# TG3_2.net
KiCad netlist of a schematic drawn in EAGLE
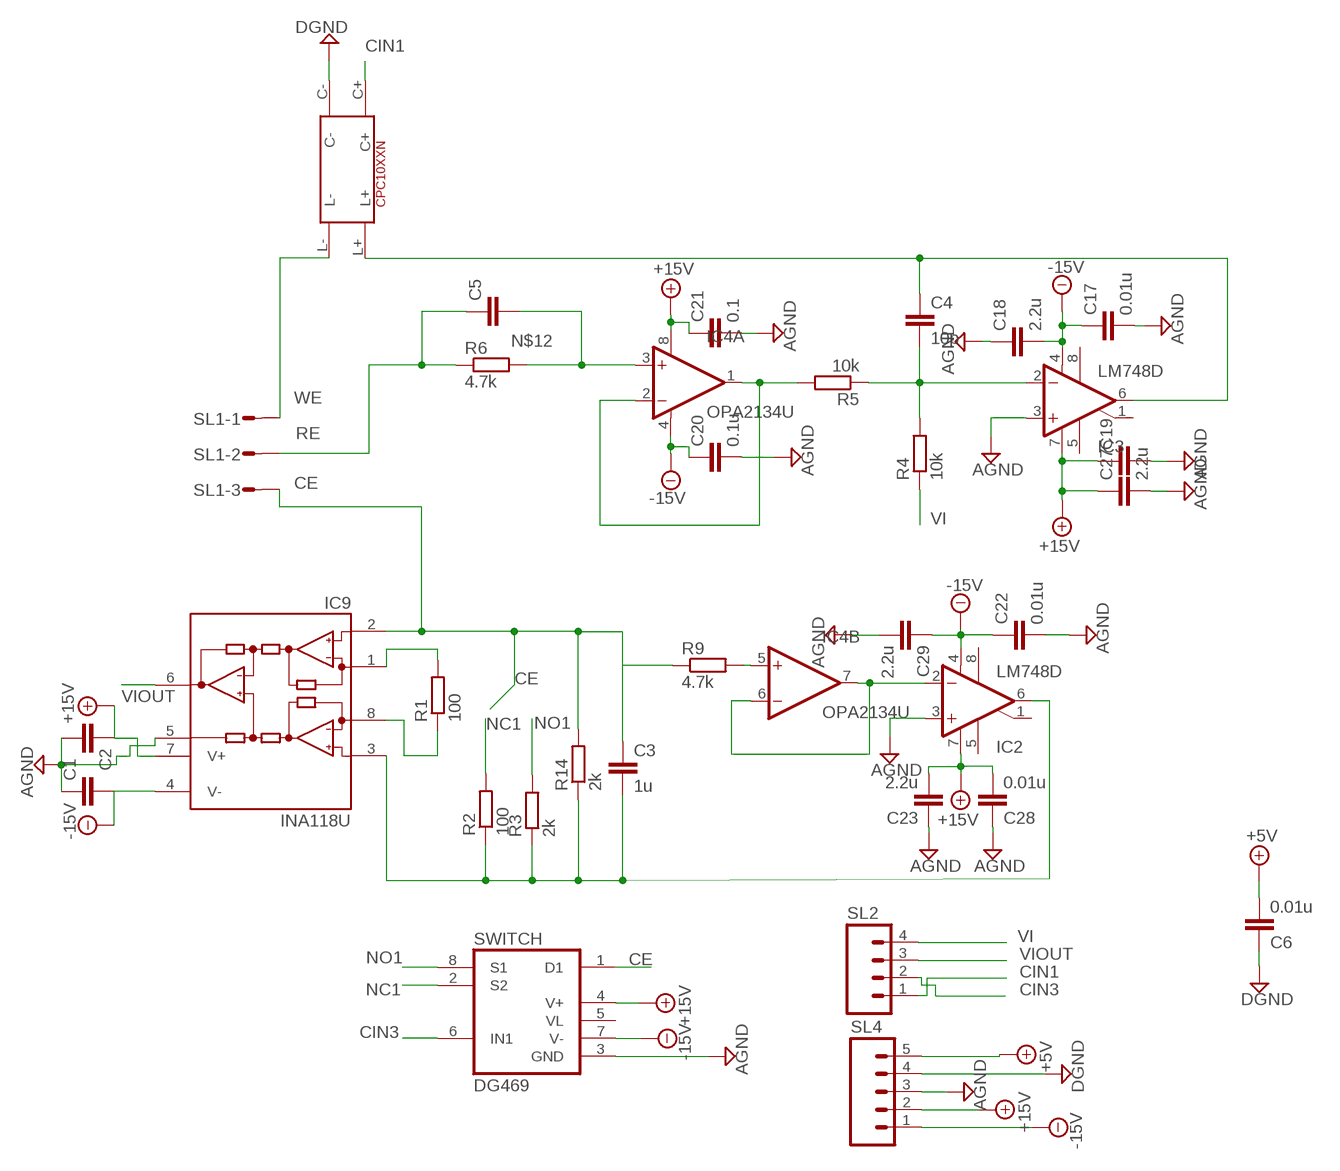
[diagram p0: schematic, sheet 1]

(export (version "E")
  (design (tool "Eeschema 10.0.6"))
  (components
    (comp (ref "C1") (value "C") (footprint "eagle-import:C0805") (libsource (lib "eagle-import") (part "C")))
    (comp (ref "C2") (value "C") (footprint "eagle-import:C0805") (libsource (lib "eagle-import") (part "C")))
    (comp (ref "C3")
      (value "1u")
      (footprint "eagle-import:C0805")
      (libsource (lib "eagle-import") (part "C"))
    )
    (comp (ref "C4")
      (value "10p")
      (footprint "eagle-import:C0805")
      (libsource (lib "eagle-import") (part "C"))
    )
    (comp (ref "C5") (value "C") (footprint "eagle-import:C0805") (libsource (lib "eagle-import") (part "C")))
    (comp (ref "C6")
      (value "0.01u")
      (footprint "eagle-import:C0805")
      (libsource (lib "eagle-import") (part "C"))
    )
    (comp (ref "C17")
      (value "0.01u")
      (footprint "eagle-import:C0805")
      (libsource (lib "eagle-import") (part "C"))
    )
    (comp (ref "C18")
      (value "2.2u")
      (footprint "eagle-import:C0805")
      (libsource (lib "eagle-import") (part "C"))
    )
    (comp (ref "C19")
      (value "C")
      (footprint "eagle-import:C0805")
      (libsource (lib "eagle-import") (part "C"))
    )
    (comp (ref "C20")
      (value "0.1u")
      (footprint "eagle-import:C0805")
      (libsource (lib "eagle-import") (part "C"))
    )
    (comp (ref "C21")
      (value "0.1")
      (footprint "eagle-import:C0805")
      (libsource (lib "eagle-import") (part "C"))
    )
    (comp (ref "C22")
      (value "0.01u")
      (footprint "eagle-import:C0805")
      (libsource (lib "eagle-import") (part "C"))
    )
    (comp (ref "C23")
      (value "2.2u")
      (footprint "eagle-import:C0805")
      (libsource (lib "eagle-import") (part "C"))
    )
    (comp (ref "C27")
      (value "2.2u")
      (footprint "eagle-import:C0805")
      (libsource (lib "eagle-import") (part "C"))
    )
    (comp (ref "C28")
      (value "0.01u")
      (footprint "eagle-import:C0805")
      (libsource (lib "eagle-import") (part "C"))
    )
    (comp (ref "C29")
      (value "2.2u")
      (footprint "eagle-import:C0805")
      (libsource (lib "eagle-import") (part "C"))
    )
    (comp (ref "IC2")
      (value "LM748D")
      (footprint "eagle-import:SO08")
      (libsource (lib "eagle-import") (part "748DLM"))
    )
    (comp (ref "IC3")
      (value "LM748D")
      (footprint "eagle-import:SO08")
      (libsource (lib "eagle-import") (part "748DLM"))
    )
    (comp (ref "IC4")
      (value "OPA2134U")
      (footprint "eagle-import:SO08")
      (fields (field (name "MF") "TEXAS INSTRUMENTS") (field (name "MPN") "OPA2134UA"))
      (libsource (lib "eagle-import") (part "OPA2134U"))
    )
    (comp (ref "IC9")
      (value "INA118U")
      (footprint "eagle-import:SO08")
      (fields (field (name "MF") "TEXAS INSTRUMENTS"))
      (libsource (lib "eagle-import") (part "INA118U"))
    )
    (comp (ref "R1")
      (value "100")
      (footprint "eagle-import:R0805")
      (libsource (lib "eagle-import") (part "R"))
    )
    (comp (ref "R2")
      (value "100")
      (footprint "eagle-import:R0805")
      (libsource (lib "eagle-import") (part "R"))
    )
    (comp (ref "R3")
      (value "2k")
      (footprint "eagle-import:R0805")
      (libsource (lib "eagle-import") (part "R"))
    )
    (comp (ref "R4")
      (value "10k")
      (footprint "eagle-import:R0805")
      (libsource (lib "eagle-import") (part "R"))
    )
    (comp (ref "R5")
      (value "10k")
      (footprint "eagle-import:R0805")
      (libsource (lib "eagle-import") (part "R"))
    )
    (comp (ref "R6")
      (value "4.7k")
      (footprint "eagle-import:R0805")
      (libsource (lib "eagle-import") (part "R"))
    )
    (comp (ref "R9")
      (value "4.7k")
      (footprint "eagle-import:R0805")
      (libsource (lib "eagle-import") (part "R"))
    )
    (comp (ref "R14")
      (value "2k")
      (footprint "eagle-import:R0805")
      (libsource (lib "eagle-import") (part "R"))
    )
    (comp (ref "SL1")
      (value "M03S")
      (footprint "eagle-import:03P")
      (libsource (lib "eagle-import") (part "M03S"))
    )
    (comp (ref "SL2")
      (value "M04")
      (footprint "eagle-import:04P")
      (libsource (lib "eagle-import") (part "M04"))
    )
    (comp (ref "SL4")
      (value "M05")
      (footprint "eagle-import:05P")
      (libsource (lib "eagle-import") (part "M05"))
    )
    (comp (ref "SWITCH")
      (value "DG469")
      (footprint "eagle-import:SO08")
      (libsource (lib "eagle-import") (part "DG469"))
    )
    (comp (ref "U$5")
      (value "CPC10XXN")
      (footprint "eagle-import:CPC10XXN")
      (libsource (lib "eagle-import") (part "CPC10XXN"))
    )
  )
  (nets
    (net (code "1") (name "+5V") (class "Default")
      (node (ref "C6") (pin "2") (pinfunction "2_2") (pintype "passive"))
      (node (ref "SL4") (pin "5") (pinfunction "5_5") (pintype "passive"))
    )
    (net (code "2") (name "+15V") (class "Default")
      (node (ref "C19") (pin "1") (pinfunction "1_1") (pintype "passive"))
      (node (ref "C2") (pin "1") (pinfunction "1_1") (pintype "passive"))
      (node (ref "C21") (pin "1") (pinfunction "1_1") (pintype "passive"))
      (node (ref "C23") (pin "2") (pinfunction "2_2") (pintype "passive"))
      (node (ref "C27") (pin "1") (pinfunction "1_1") (pintype "passive"))
      (node (ref "C28") (pin "2") (pinfunction "2_2") (pintype "passive"))
      (node (ref "IC2") (pin "7") (pinfunction "V+_7") (pintype "power_in"))
      (node (ref "IC3") (pin "7") (pinfunction "V+_7") (pintype "power_in"))
      (node (ref "IC4") (pin "8") (pinfunction "V+_8") (pintype "power_in"))
      (node (ref "IC9") (pin "7") (pinfunction "V+_7") (pintype "power_in"))
      (node (ref "SL4") (pin "2") (pinfunction "2_2") (pintype "passive"))
      (node (ref "SWITCH") (pin "4") (pinfunction "V+_4") (pintype "power_in"))
    )
    (net (code "3") (name "-15V") (class "Default")
      (node (ref "C1") (pin "2") (pinfunction "2_2") (pintype "passive"))
      (node (ref "C17") (pin "1") (pinfunction "1_1") (pintype "passive"))
      (node (ref "C18") (pin "2") (pinfunction "2_2") (pintype "passive"))
      (node (ref "C20") (pin "1") (pinfunction "1_1") (pintype "passive"))
      (node (ref "C22") (pin "1") (pinfunction "1_1") (pintype "passive"))
      (node (ref "C29") (pin "1") (pinfunction "1_1") (pintype "passive"))
      (node (ref "IC2") (pin "4") (pinfunction "V-_4") (pintype "power_in"))
      (node (ref "IC3") (pin "4") (pinfunction "V-_4") (pintype "power_in"))
      (node (ref "IC4") (pin "4") (pinfunction "V-_4") (pintype "power_in"))
      (node (ref "IC9") (pin "4") (pinfunction "V-_4") (pintype "power_in"))
      (node (ref "SL4") (pin "1") (pinfunction "1_1") (pintype "passive"))
      (node (ref "SWITCH") (pin "7") (pinfunction "V-_7") (pintype "power_in"))
    )
    (net (code "4") (name "/CE") (class "Default")
      (node (ref "C3") (pin "1") (pinfunction "1_1") (pintype "passive"))
      (node (ref "IC9") (pin "2") (pinfunction "-IN_2") (pintype "input"))
      (node (ref "R14") (pin "2") (pinfunction "2_2") (pintype "passive"))
      (node (ref "R9") (pin "1") (pinfunction "1_1") (pintype "passive"))
      (node (ref "SL1") (pin "3") (pinfunction "S_3") (pintype "passive"))
      (node (ref "SWITCH") (pin "1") (pinfunction "D1_1") (pintype "passive"))
    )
    (net (code "5") (name "/CIN1") (class "Default")
      (node (ref "SL2") (pin "1") (pinfunction "1_1") (pintype "passive"))
      (node (ref "U$5") (pin "C+") (pinfunction "C+_C+") (pintype "bidirectional"))
    )
    (net (code "6") (name "/CIN3") (class "Default")
      (node (ref "SL2") (pin "2") (pinfunction "2_2") (pintype "passive"))
      (node (ref "SWITCH") (pin "6") (pinfunction "IN1_6") (pintype "input"))
    )
    (net (code "7") (name "/N$12") (class "Default")
      (node (ref "C5") (pin "2") (pinfunction "2_2") (pintype "passive"))
      (node (ref "IC4") (pin "3") (pinfunction "+IN_3") (pintype "input"))
      (node (ref "R6") (pin "2") (pinfunction "2_2") (pintype "passive"))
    )
    (net (code "8") (name "/NC1") (class "Default")
      (node (ref "R2") (pin "2") (pinfunction "2_2") (pintype "passive"))
      (node (ref "SWITCH") (pin "2") (pinfunction "S2_2") (pintype "passive"))
    )
    (net (code "9") (name "/NO1") (class "Default")
      (node (ref "R3") (pin "2") (pinfunction "2_2") (pintype "passive"))
      (node (ref "SWITCH") (pin "8") (pinfunction "S1_8") (pintype "passive"))
    )
    (net (code "10") (name "/RE") (class "Default")
      (node (ref "C5") (pin "1") (pinfunction "1_1") (pintype "passive"))
      (node (ref "R6") (pin "1") (pinfunction "1_1") (pintype "passive"))
      (node (ref "SL1") (pin "2") (pinfunction "S_2") (pintype "passive"))
    )
    (net (code "11") (name "/VI") (class "Default")
      (node (ref "R4") (pin "1") (pinfunction "1_1") (pintype "passive"))
      (node (ref "SL2") (pin "4") (pinfunction "4_4") (pintype "passive"))
    )
    (net (code "12") (name "/VIOUT") (class "Default")
      (node (ref "IC9") (pin "6") (pinfunction "OUT_6") (pintype "output"))
      (node (ref "SL2") (pin "3") (pinfunction "3_3") (pintype "passive"))
    )
    (net (code "13") (name "/VL") (class "Default")
      (node (ref "SWITCH") (pin "5") (pinfunction "VL_5") (pintype "power_in"))
    )
    (net (code "14") (name "/WE") (class "Default")
      (node (ref "SL1") (pin "1") (pinfunction "S_1") (pintype "passive"))
      (node (ref "U$5") (pin "L-") (pinfunction "L-_L-") (pintype "bidirectional"))
    )
    (net (code "15") (name "AGND") (class "Default")
      (node (ref "C1") (pin "1") (pinfunction "1_1") (pintype "passive"))
      (node (ref "C17") (pin "2") (pinfunction "2_2") (pintype "passive"))
      (node (ref "C18") (pin "1") (pinfunction "1_1") (pintype "passive"))
      (node (ref "C19") (pin "2") (pinfunction "2_2") (pintype "passive"))
      (node (ref "C2") (pin "2") (pinfunction "2_2") (pintype "passive"))
      (node (ref "C20") (pin "2") (pinfunction "2_2") (pintype "passive"))
      (node (ref "C21") (pin "2") (pinfunction "2_2") (pintype "passive"))
      (node (ref "C22") (pin "2") (pinfunction "2_2") (pintype "passive"))
      (node (ref "C23") (pin "1") (pinfunction "1_1") (pintype "passive"))
      (node (ref "C27") (pin "2") (pinfunction "2_2") (pintype "passive"))
      (node (ref "C28") (pin "1") (pinfunction "1_1") (pintype "passive"))
      (node (ref "C29") (pin "2") (pinfunction "2_2") (pintype "passive"))
      (node (ref "IC2") (pin "3") (pinfunction "+IN_3") (pintype "input"))
      (node (ref "IC3") (pin "3") (pinfunction "+IN_3") (pintype "input"))
      (node (ref "IC9") (pin "5") (pinfunction "REF_5") (pintype "passive"))
      (node (ref "SL4") (pin "3") (pinfunction "3_3") (pintype "passive"))
      (node (ref "SWITCH") (pin "3") (pinfunction "GND_3") (pintype "power_in"))
    )
    (net (code "16") (name "DGND") (class "Default")
      (node (ref "C6") (pin "1") (pinfunction "1_1") (pintype "passive"))
      (node (ref "SL4") (pin "4") (pinfunction "4_4") (pintype "passive"))
      (node (ref "U$5") (pin "C-") (pinfunction "C-_C-") (pintype "bidirectional"))
    )
    (net (code "17") (name "Net-(IC2--IN)") (class "Default")
      (node (ref "IC2") (pin "2") (pinfunction "-IN_2") (pintype "input"))
      (node (ref "IC4") (pin "6") (pinfunction "-IN_6") (pintype "input"))
      (node (ref "IC4") (pin "7") (pinfunction "OUT_7") (pintype "output"))
    )
    (net (code "18") (name "Net-(IC2-OUT)") (class "Default")
      (node (ref "C3") (pin "2") (pinfunction "2_2") (pintype "passive"))
      (node (ref "IC2") (pin "6") (pinfunction "OUT_6") (pintype "output"))
      (node (ref "IC9") (pin "3") (pinfunction "+IN_3") (pintype "input"))
      (node (ref "R14") (pin "1") (pinfunction "1_1") (pintype "passive"))
      (node (ref "R2") (pin "1") (pinfunction "1_1") (pintype "passive"))
      (node (ref "R3") (pin "1") (pinfunction "1_1") (pintype "passive"))
    )
    (net (code "19") (name "Net-(IC3--IN)") (class "Default")
      (node (ref "C4") (pin "2") (pinfunction "2_2") (pintype "passive"))
      (node (ref "IC3") (pin "2") (pinfunction "-IN_2") (pintype "input"))
      (node (ref "R4") (pin "2") (pinfunction "2_2") (pintype "passive"))
      (node (ref "R5") (pin "1") (pinfunction "1_1") (pintype "passive"))
    )
    (net (code "20") (name "Net-(IC3-OUT)") (class "Default")
      (node (ref "C4") (pin "1") (pinfunction "1_1") (pintype "passive"))
      (node (ref "IC3") (pin "6") (pinfunction "OUT_6") (pintype "output"))
      (node (ref "U$5") (pin "L+") (pinfunction "L+_L+") (pintype "bidirectional"))
    )
    (net (code "21") (name "Net-(IC4A--IN)") (class "Default")
      (node (ref "IC4") (pin "1") (pinfunction "OUT_1") (pintype "output"))
      (node (ref "IC4") (pin "2") (pinfunction "-IN_2") (pintype "input"))
      (node (ref "R5") (pin "2") (pinfunction "2_2") (pintype "passive"))
    )
    (net (code "22") (name "Net-(IC4B-+IN)") (class "Default")
      (node (ref "IC4") (pin "5") (pinfunction "+IN_5") (pintype "input"))
      (node (ref "R9") (pin "2") (pinfunction "2_2") (pintype "passive"))
    )
    (net (code "23") (name "Net-(IC9-RG-Pad1)") (class "Default")
      (node (ref "IC9") (pin "1") (pinfunction "RG_1") (pintype "passive"))
      (node (ref "R1") (pin "2") (pinfunction "2_2") (pintype "passive"))
    )
    (net (code "24") (name "Net-(IC9-RG-Pad8)") (class "Default")
      (node (ref "IC9") (pin "8") (pinfunction "RG_8") (pintype "passive"))
      (node (ref "R1") (pin "1") (pinfunction "1_1") (pintype "passive"))
    )
    (net (code "25") (name "unconnected-(IC2-CMP-Pad8)") (class "Default")
      (node (ref "IC2") (pin "8") (pinfunction "CMP_8") (pintype "passive"))
    )
    (net (code "26") (name "unconnected-(IC2-ON-Pad5)") (class "Default")
      (node (ref "IC2") (pin "5") (pinfunction "ON_5") (pintype "passive"))
    )
    (net (code "27") (name "unconnected-(IC2-ON{slash}CMP-Pad1)") (class "Default")
      (node (ref "IC2") (pin "1") (pinfunction "ON/CMP_1") (pintype "passive"))
    )
    (net (code "28") (name "unconnected-(IC3-CMP-Pad8)") (class "Default")
      (node (ref "IC3") (pin "8") (pinfunction "CMP_8") (pintype "passive"))
    )
    (net (code "29") (name "unconnected-(IC3-ON-Pad5)") (class "Default")
      (node (ref "IC3") (pin "5") (pinfunction "ON_5") (pintype "passive"))
    )
    (net (code "30") (name "unconnected-(IC3-ON{slash}CMP-Pad1)") (class "Default")
      (node (ref "IC3") (pin "1") (pinfunction "ON/CMP_1") (pintype "passive"))
    )
  )
)
